# PCB_SATA_SFP.net
KiCad netlist of a schematic drawn in Altium Designer
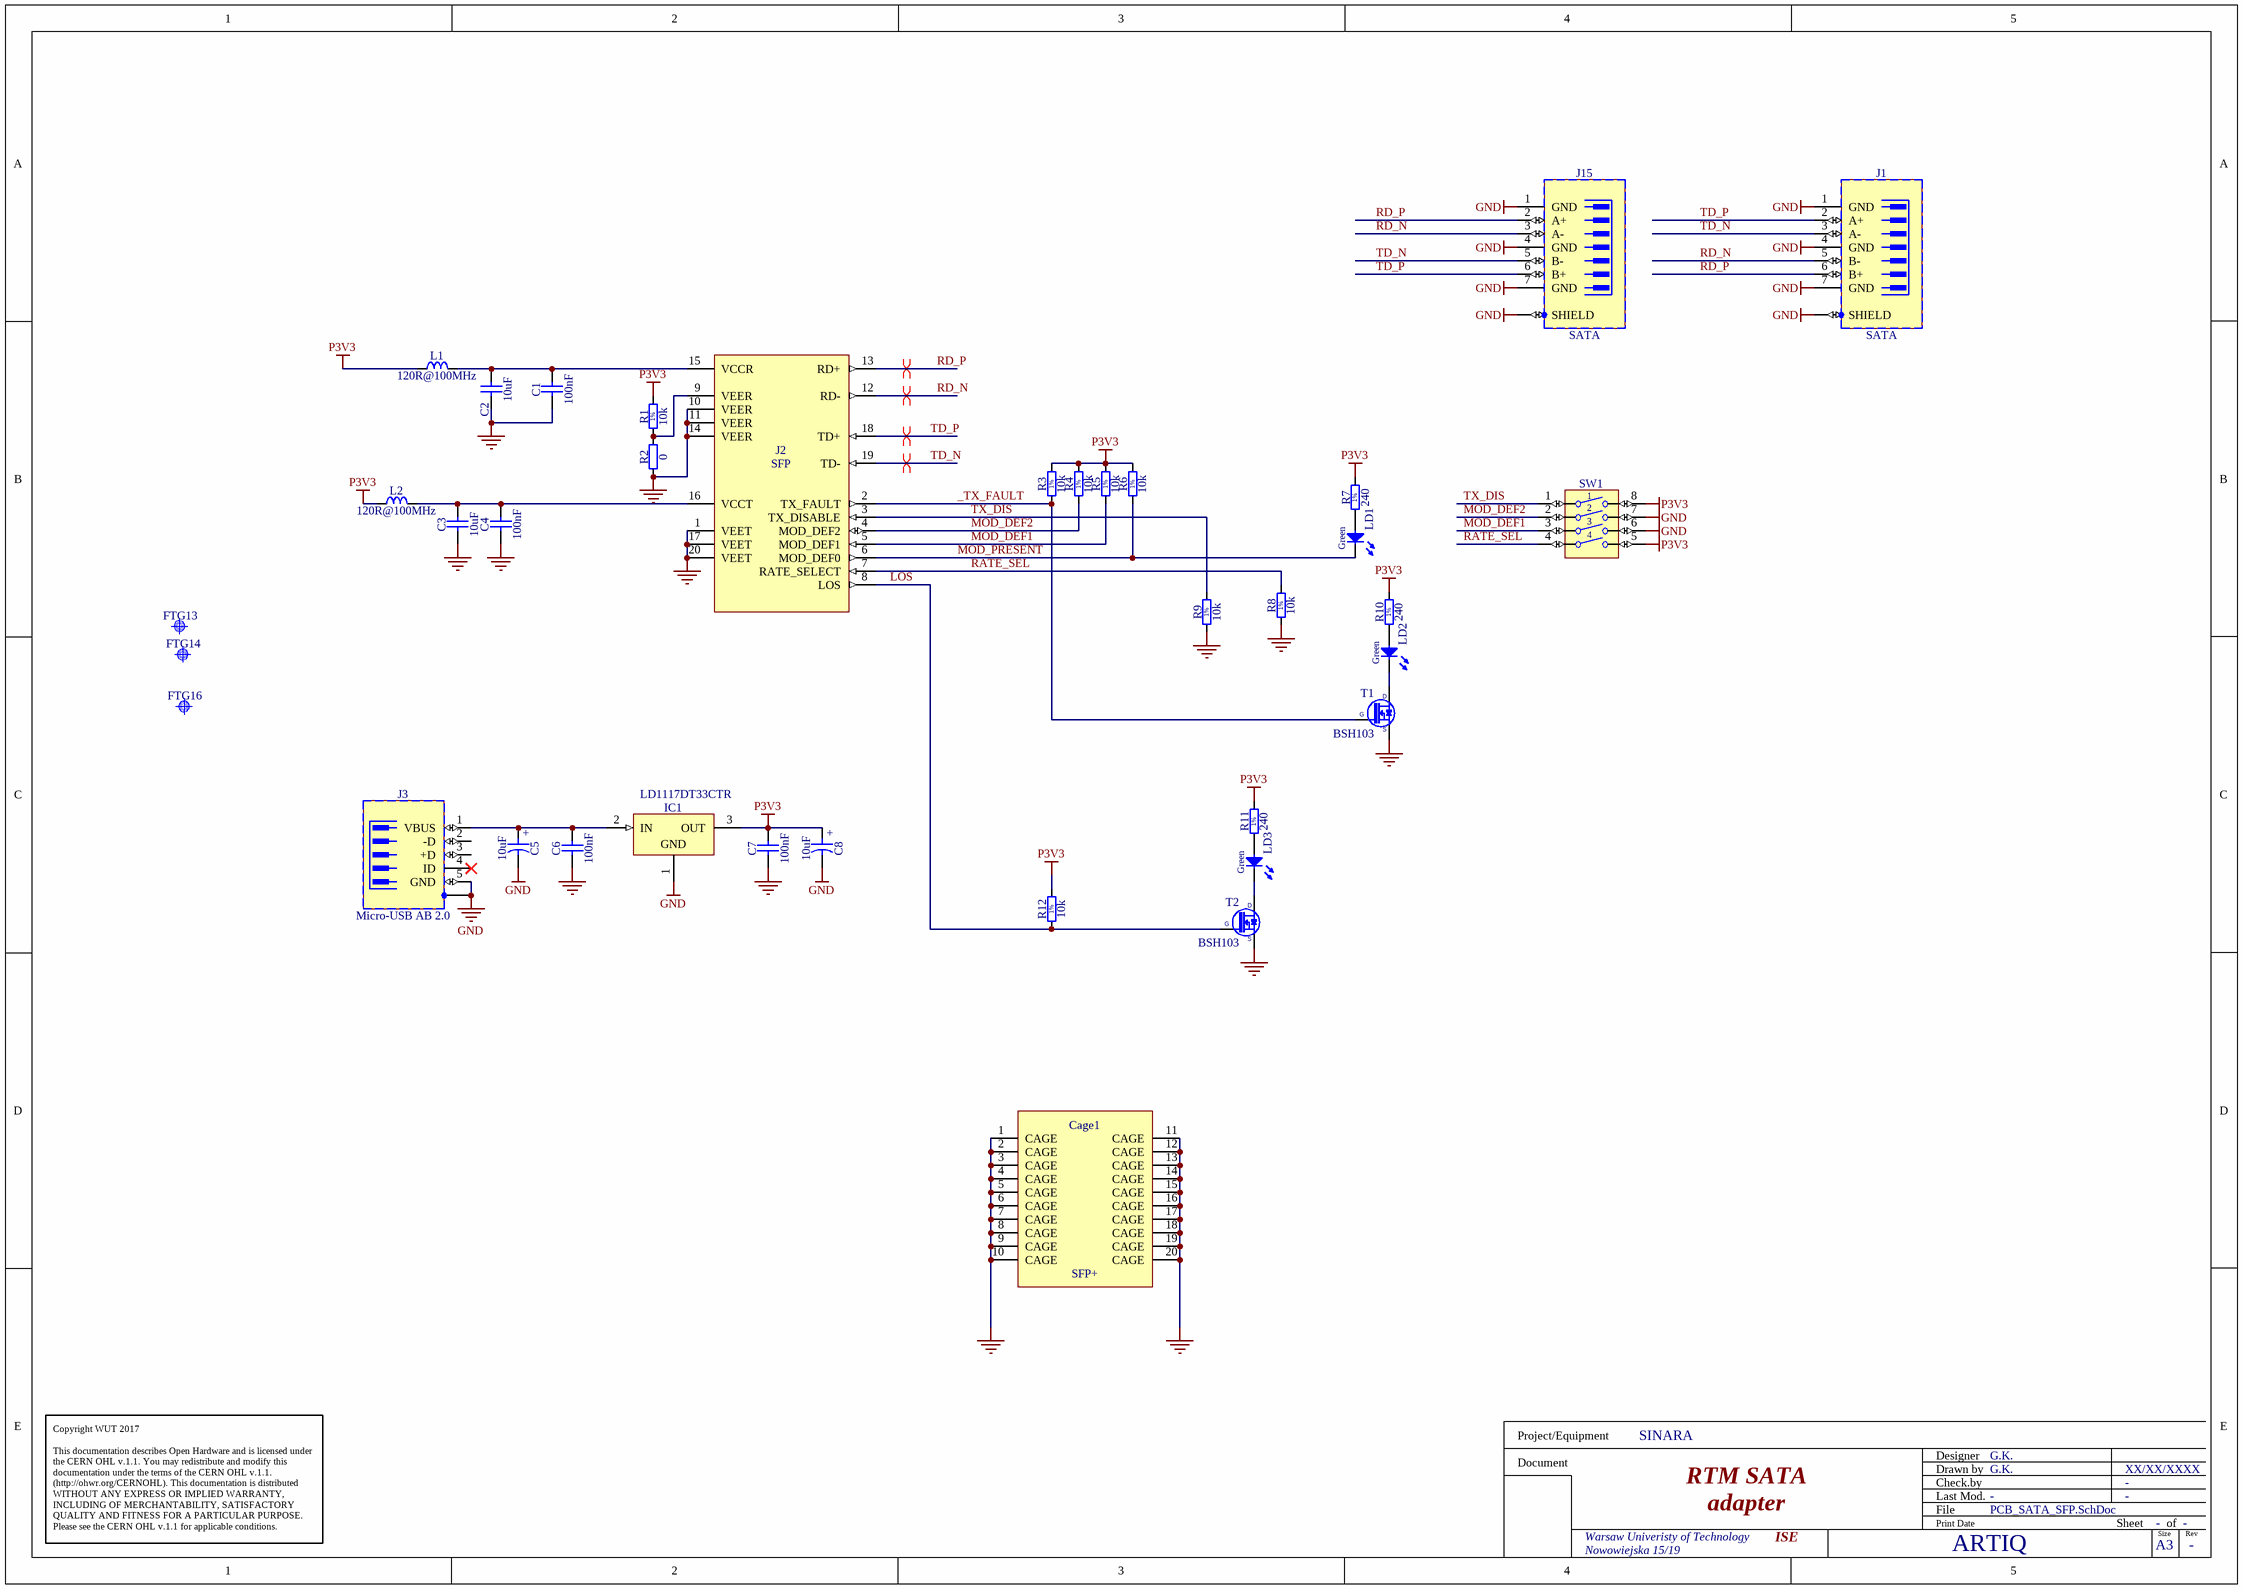
[diagram p0: PCB_SATA_SFP.SchDoc]

(export (version "E")
  (design (tool "Eeschema 10.0.6"))
  (components
    (comp (ref "C1")
      (value "100nF")
      (footprint "CAPC1608X87N")
      (description "Non-polarised capacitor")
      (fields
        (field (name "PART NUMBER") "CC0603_100NF_50V_10%_X5R")
        (field (name "VOLTAGE") "50V")
        (field (name "AUTHOR") "CERN DEM MR")
      )
      (libsource (lib "Capacitors") (part "Capacitor - non polarized"))
    )
    (comp (ref "C2")
      (value "10uF")
      (footprint "CAPC2012X95N")
      (description "Non-polarised capacitor")
      (fields
        (field (name "PART NUMBER") "CC0805_10UF_25V_10%_X5R")
        (field (name "VOLTAGE") "25V")
        (field (name "AUTHOR") "CERN DEM JLC")
      )
      (libsource (lib "Capacitors") (part "Capacitor - non polarized"))
    )
    (comp (ref "C3")
      (value "10uF")
      (footprint "CAPC2012X95N")
      (description "Non-polarised capacitor")
      (fields
        (field (name "PART NUMBER") "CC0805_10UF_25V_10%_X5R")
        (field (name "VOLTAGE") "25V")
        (field (name "AUTHOR") "CERN DEM JLC")
      )
      (libsource (lib "Capacitors") (part "Capacitor - non polarized"))
    )
    (comp (ref "C4")
      (value "100nF")
      (footprint "CAPC1608X87N")
      (description "Non-polarised capacitor")
      (fields
        (field (name "PART NUMBER") "CC0603_100NF_50V_10%_X5R")
        (field (name "VOLTAGE") "50V")
        (field (name "AUTHOR") "CERN DEM MR")
      )
      (libsource (lib "Capacitors") (part "Capacitor - non polarized"))
    )
    (comp (ref "C5")
      (value "10uF")
      (footprint "CAPMP6032X280N")
      (description "Polarised capacitor")
      (fields
        (field (name "PART NUMBER") "CTE6032-28_10UF_25V_10%_LESR0300")
        (field (name "VOLTAGE") "25V")
        (field (name "AUTHOR") "CERN DEM JLC")
      )
      (libsource (lib "Capacitors") (part "Capacitor - polarized"))
    )
    (comp (ref "C6")
      (value "100nF")
      (footprint "CAPC1608X87N")
      (description "Non-polarised capacitor")
      (fields
        (field (name "PART NUMBER") "CC0603_100NF_50V_10%_X5R")
        (field (name "VOLTAGE") "50V")
        (field (name "AUTHOR") "CERN DEM MR")
      )
      (libsource (lib "Capacitors") (part "Capacitor - non polarized"))
    )
    (comp (ref "C7")
      (value "100nF")
      (footprint "CAPC1608X87N")
      (description "Non-polarised capacitor")
      (fields
        (field (name "PART NUMBER") "CC0603_100NF_50V_10%_X5R")
        (field (name "VOLTAGE") "50V")
        (field (name "AUTHOR") "CERN DEM MR")
      )
      (libsource (lib "Capacitors") (part "Capacitor - non polarized"))
    )
    (comp (ref "C8")
      (value "10uF")
      (footprint "CAPMP6032X280N")
      (description "Polarised capacitor")
      (fields
        (field (name "PART NUMBER") "CTE6032-28_10UF_25V_10%_LESR0300")
        (field (name "VOLTAGE") "25V")
        (field (name "AUTHOR") "CERN DEM JLC")
      )
      (libsource (lib "Capacitors") (part "Capacitor - polarized"))
    )
    (comp (ref "Cage1")
      (value "SFP+")
      (footprint "TYCO_2007198-1")
      (description "SFP+ 1x1 Cage (20Pins)")
      (fields
        (field (name "PART NUMBER") "TYCO_2007198-1")
        (field (name "MANUFACTURER") "TYCO ELECTRONICS")
        (field (name "AUTHOR") "CERN DEM JLC")
      )
      (libsource (lib "Connectors") (part "SFP+ 1x1 Cage (20Pins)"))
    )
    (comp (ref "FTG13")
      (value "Use only in PCB")
      (footprint "FIDUCIAL_TOP_C100-200")
      (description "Fiducial Target")
      (fields (field (name "PART NUMBER") "FIDUCIAL_TARGET_C100-200") (field (name "AUTHOR") "CERN DEM JLC"))
      (libsource (lib "Eletro-mechanical") (part "Fiducial Target"))
    )
    (comp (ref "FTG14")
      (value "Use only in PCB")
      (footprint "FIDUCIAL_TOP_S100-200")
      (description "Fiducial Target")
      (fields (field (name "PART NUMBER") "FIDUCIAL_TARGET_S100-200") (field (name "AUTHOR") "CERN DEM JLC"))
      (libsource (lib "Eletro-mechanical") (part "Fiducial Target"))
    )
    (comp (ref "FTG16")
      (value "Use only in PCB")
      (footprint "FIDUCIAL_TOP_S100-200")
      (description "Fiducial Target")
      (fields (field (name "PART NUMBER") "FIDUCIAL_TARGET_S100-200") (field (name "AUTHOR") "CERN DEM JLC"))
      (libsource (lib "Eletro-mechanical") (part "Fiducial Target"))
    )
    (comp (ref "IC1")
      (value "LD1117DT33CTR")
      (footprint "TO228P972X240-3N-R540X510")
      (description "3-Terminal Regulator 1=GND 2=IN 3=OUT")
      (fields (field (name "MANUFACTURER") "ST MICROELECTRONICS") (field (name "AUTHOR") "CERN DEM JLC"))
      (libsource (lib "ICs And Semiconductors") (part "REG3 1GND-2IN-3OUT"))
    )
    (comp (ref "J1")
      (value "SATA")
      (footprint "3M_5607-4200-SH")
      (description "7 Pin + 1 Shield SATA Receptacle")
      (fields
        (field (name "PART NUMBER") "3M_5607-4200-SH")
        (field (name "MANUFACTURER") "3M")
        (field (name "AUTHOR") "CERN DEM JLC")
      )
      (libsource (lib "Connectors") (part "Connector SATA 7 Male + 1 Shield"))
    )
    (comp (ref "J2")
      (value "SFP")
      (footprint "TYCO_1367073-1")
      (description "20 Position SFP  Connector (Small Form-factor Pluggable)")
      (fields
        (field (name "PART NUMBER") "TYCO_1367073-1")
        (field (name "MANUFACTURER") "TYCO ELECTRONICS")
        (field (name "AUTHOR") "CERN DEM JLC")
      )
      (libsource (lib "Connectors") (part "SFPx1"))
    )
    (comp (ref "J3")
      (value "Micro-USB AB 2.0")
      (footprint "HIROSE_ZX62RD-AB-5P8")
      (description "5 Pin + 1 Shield USB Receptacle")
      (fields
        (field (name "PART NUMBER") "HIROSE_ZX62RD-AB-5P8")
        (field (name "MANUFACTURER") "HIROSE (HRS)")
        (field (name "AUTHOR") "CERN DEM JLC")
      )
      (libsource (lib "Connectors") (part "Connector USB 5 Pin + 1Shield"))
    )
    (comp (ref "J15")
      (value "SATA")
      (footprint "3M_5607-4200-SH")
      (description "7 Pin + 1 Shield SATA Receptacle")
      (fields
        (field (name "PART NUMBER") "3M_5607-4200-SH")
        (field (name "MANUFACTURER") "3M")
        (field (name "AUTHOR") "CERN DEM JLC")
      )
      (libsource (lib "Connectors") (part "Connector SATA 7 Male + 1 Shield"))
    )
    (comp (ref "L1")
      (value "120R@100MHz")
      (footprint "INDC1608X65N")
      (description "Inductor")
      (fields
        (field (name "PART NUMBER") "IND0603_MURATA_BLM18SG121TN1D")
        (field (name "POWER") "3A")
        (field (name "AUTHOR") "CERN DEM JLC")
      )
      (libsource (lib "Inductors & Transformers") (part "Inductor"))
    )
    (comp (ref "L2")
      (value "120R@100MHz")
      (footprint "INDC1608X65N")
      (description "Inductor")
      (fields
        (field (name "PART NUMBER") "IND0603_MURATA_BLM18SG121TN1D")
        (field (name "POWER") "3A")
        (field (name "AUTHOR") "CERN DEM JLC")
      )
      (libsource (lib "Inductors & Transformers") (part "Inductor"))
    )
    (comp (ref "LD1")
      (value "Green")
      (footprint "LED_KINGBRIGHT_KPH-1608CGCK")
      (description "LED Green 1C 2A")
      (fields
        (field (name "PART NUMBER") "LED_KINGBRIGHT_KPH-1608CGCK")
        (field (name "MANUFACTURER") "KINGBRIGHT")
        (field (name "AUTHOR") "CERN DEM JLC")
      )
      (libsource (lib "ICs And Semiconductors") (part "LED Green 1C 2A"))
    )
    (comp (ref "LD2")
      (value "Green")
      (footprint "LED_KINGBRIGHT_KPH-1608CGCK")
      (description "LED Green 1C 2A")
      (fields
        (field (name "PART NUMBER") "LED_KINGBRIGHT_KPH-1608CGCK")
        (field (name "MANUFACTURER") "KINGBRIGHT")
        (field (name "AUTHOR") "CERN DEM JLC")
      )
      (libsource (lib "ICs And Semiconductors") (part "LED Green 1C 2A"))
    )
    (comp (ref "LD3")
      (value "Green")
      (footprint "LED_KINGBRIGHT_KPH-1608CGCK")
      (description "LED Green 1C 2A")
      (fields
        (field (name "PART NUMBER") "LED_KINGBRIGHT_KPH-1608CGCK")
        (field (name "MANUFACTURER") "KINGBRIGHT")
        (field (name "AUTHOR") "CERN DEM JLC")
      )
      (libsource (lib "ICs And Semiconductors") (part "LED Green 1C 2A"))
    )
    (comp (ref "R1")
      (value "10k")
      (footprint "RESC1608X55N")
      (description "Resistor - 1%")
      (fields
        (field (name "PART NUMBER") "R0603_10K_1%_0.1W_100PPM")
        (field (name "POWER") "0.1W")
        (field (name "AUTHOR") "CERN DEM JLC")
      )
      (libsource (lib "Resistors") (part "Resistor - 1%"))
    )
    (comp (ref "R2")
      (value "0")
      (footprint "RESC1608X55N")
      (description "Resistor")
      (fields
        (field (name "PART NUMBER") "R0603_0R_JUMPER")
        (field (name "MANUFACTURER") "GENERIC")
        (field (name "AUTHOR") "CERN DEM JLC")
      )
      (libsource (lib "Resistors") (part "Resistor"))
    )
    (comp (ref "R3")
      (value "10k")
      (footprint "RESC1608X55N")
      (description "Resistor - 1%")
      (fields
        (field (name "PART NUMBER") "R0603_10K_1%_0.1W_100PPM")
        (field (name "POWER") "0.1W")
        (field (name "AUTHOR") "CERN DEM JLC")
      )
      (libsource (lib "Resistors") (part "Resistor - 1%"))
    )
    (comp (ref "R4")
      (value "10k")
      (footprint "RESC1608X55N")
      (description "Resistor - 1%")
      (fields
        (field (name "PART NUMBER") "R0603_10K_1%_0.1W_100PPM")
        (field (name "POWER") "0.1W")
        (field (name "AUTHOR") "CERN DEM JLC")
      )
      (libsource (lib "Resistors") (part "Resistor - 1%"))
    )
    (comp (ref "R5")
      (value "10k")
      (footprint "RESC1608X55N")
      (description "Resistor - 1%")
      (fields
        (field (name "PART NUMBER") "R0603_10K_1%_0.1W_100PPM")
        (field (name "POWER") "0.1W")
        (field (name "AUTHOR") "CERN DEM JLC")
      )
      (libsource (lib "Resistors") (part "Resistor - 1%"))
    )
    (comp (ref "R6")
      (value "10k")
      (footprint "RESC1608X55N")
      (description "Resistor - 1%")
      (fields
        (field (name "PART NUMBER") "R0603_10K_1%_0.1W_100PPM")
        (field (name "POWER") "0.1W")
        (field (name "AUTHOR") "CERN DEM JLC")
      )
      (libsource (lib "Resistors") (part "Resistor - 1%"))
    )
    (comp (ref "R7")
      (value "240")
      (footprint "RESC1608X55N")
      (description "Resistor - 1%")
      (fields
        (field (name "PART NUMBER") "R0603_240R_1%_0.1W_100PPM")
        (field (name "POWER") "0.1W")
        (field (name "AUTHOR") "CERN DEM JLC")
      )
      (libsource (lib "Resistors") (part "Resistor - 1%"))
    )
    (comp (ref "R8")
      (value "10k")
      (footprint "RESC1608X55N")
      (description "Resistor - 1%")
      (fields
        (field (name "PART NUMBER") "R0603_10K_1%_0.1W_100PPM")
        (field (name "POWER") "0.1W")
        (field (name "AUTHOR") "CERN DEM JLC")
      )
      (libsource (lib "Resistors") (part "Resistor - 1%"))
    )
    (comp (ref "R9")
      (value "10k")
      (footprint "RESC1608X55N")
      (description "Resistor - 1%")
      (fields
        (field (name "PART NUMBER") "R0603_10K_1%_0.1W_100PPM")
        (field (name "POWER") "0.1W")
        (field (name "AUTHOR") "CERN DEM JLC")
      )
      (libsource (lib "Resistors") (part "Resistor - 1%"))
    )
    (comp (ref "R10")
      (value "240")
      (footprint "RESC1608X55N")
      (description "Resistor - 1%")
      (fields
        (field (name "PART NUMBER") "R0603_240R_1%_0.1W_100PPM")
        (field (name "POWER") "0.1W")
        (field (name "AUTHOR") "CERN DEM JLC")
      )
      (libsource (lib "Resistors") (part "Resistor - 1%"))
    )
    (comp (ref "R11")
      (value "240")
      (footprint "RESC1608X55N")
      (description "Resistor - 1%")
      (fields
        (field (name "PART NUMBER") "R0603_240R_1%_0.1W_100PPM")
        (field (name "POWER") "0.1W")
        (field (name "AUTHOR") "CERN DEM JLC")
      )
      (libsource (lib "Resistors") (part "Resistor - 1%"))
    )
    (comp (ref "R12")
      (value "10k")
      (footprint "RESC1608X55N")
      (description "Resistor - 1%")
      (fields
        (field (name "PART NUMBER") "R0603_10K_1%_0.1W_100PPM")
        (field (name "POWER") "0.1W")
        (field (name "AUTHOR") "CERN DEM JLC")
      )
      (libsource (lib "Resistors") (part "Resistor - 1%"))
    )
    (comp (ref "SW1")
      (value "Switch")
      (footprint "SW_CTS_219-4MST")
      (description "4 Ways SPST DIP Switch")
      (fields
        (field (name "PART NUMBER") "SW_CTS_219-4MST")
        (field (name "MANUFACTURER") "CTS ELECTROCOMPONENTS")
        (field (name "AUTHOR") "CERN DEM JLC")
      )
      (libsource (lib "Eletro-mechanical") (part "SW 4x SPST DIP Switch"))
    )
    (comp (ref "T1")
      (value "BSH103")
      (footprint "SOT95P230X110-3N")
      (description "N-CHANNEL MOSFET WITH DIODE")
      (fields (field (name "MANUFACTURER") "NEXPERIA") (field (name "AUTHOR") "CERN DEM JLC"))
      (libsource (lib "ICs And Semiconductors") (part "N-MOSFET-D 1G 2S 3D"))
    )
    (comp (ref "T2")
      (value "BSH103")
      (footprint "SOT95P230X110-3N")
      (description "N-CHANNEL MOSFET WITH DIODE")
      (fields (field (name "MANUFACTURER") "NEXPERIA") (field (name "AUTHOR") "CERN DEM JLC"))
      (libsource (lib "ICs And Semiconductors") (part "N-MOSFET-D 1G 2S 3D"))
    )
  )
  (nets
    (net (code "1") (name "/LOS") (class "Default")
      (node (ref "J2") (pin "8") (pinfunction "LOS_8") (pintype "output"))
      (node (ref "R12") (pin "1") (pinfunction "1_1") (pintype "passive"))
      (node (ref "T2") (pin "1") (pinfunction "G_1") (pintype "passive"))
    )
    (net (code "2") (name "/MOD_DEF1") (class "Default")
      (node (ref "J2") (pin "5") (pinfunction "MOD_DEF1_5") (pintype "input"))
      (node (ref "R5") (pin "1") (pinfunction "1_1") (pintype "passive"))
      (node (ref "SW1") (pin "3") (pinfunction "3_3") (pintype "bidirectional"))
    )
    (net (code "3") (name "/MOD_DEF2") (class "Default")
      (node (ref "J2") (pin "4") (pinfunction "MOD_DEF2_4") (pintype "bidirectional"))
      (node (ref "R4") (pin "1") (pinfunction "1_1") (pintype "passive"))
      (node (ref "SW1") (pin "2") (pinfunction "2_2") (pintype "bidirectional"))
    )
    (net (code "4") (name "/MOD_PRESENT") (class "Default")
      (node (ref "J2") (pin "6") (pinfunction "MOD_DEF0_6") (pintype "output"))
      (node (ref "LD1") (pin "1") (pinfunction "C_1") (pintype "passive"))
      (node (ref "R6") (pin "1") (pinfunction "1_1") (pintype "passive"))
    )
    (net (code "5") (name "/RATE_SEL") (class "Default")
      (node (ref "J2") (pin "7") (pinfunction "RATE_SELECT_7") (pintype "input"))
      (node (ref "R8") (pin "2") (pinfunction "2_2") (pintype "passive"))
      (node (ref "SW1") (pin "4") (pinfunction "4_4") (pintype "bidirectional"))
    )
    (net (code "6") (name "/RD_N") (class "Default")
      (node (ref "J1") (pin "5") (pinfunction "B-_5") (pintype "bidirectional"))
      (node (ref "J15") (pin "3") (pinfunction "A-_3") (pintype "bidirectional"))
      (node (ref "J2") (pin "12") (pinfunction "RD-_12") (pintype "output"))
    )
    (net (code "7") (name "/RD_P") (class "Default")
      (node (ref "J1") (pin "6") (pinfunction "B+_6") (pintype "bidirectional"))
      (node (ref "J15") (pin "2") (pinfunction "A+_2") (pintype "bidirectional"))
      (node (ref "J2") (pin "13") (pinfunction "RD+_13") (pintype "output"))
    )
    (net (code "8") (name "/TD_N") (class "Default")
      (node (ref "J1") (pin "3") (pinfunction "A-_3") (pintype "bidirectional"))
      (node (ref "J15") (pin "5") (pinfunction "B-_5") (pintype "bidirectional"))
      (node (ref "J2") (pin "19") (pinfunction "TD-_19") (pintype "input"))
    )
    (net (code "9") (name "/TD_P") (class "Default")
      (node (ref "J1") (pin "2") (pinfunction "A+_2") (pintype "bidirectional"))
      (node (ref "J15") (pin "6") (pinfunction "B+_6") (pintype "bidirectional"))
      (node (ref "J2") (pin "18") (pinfunction "TD+_18") (pintype "input"))
    )
    (net (code "10") (name "/TX_DIS") (class "Default")
      (node (ref "J2") (pin "3") (pinfunction "TX_DISABLE_3") (pintype "input"))
      (node (ref "R9") (pin "2") (pinfunction "2_2") (pintype "passive"))
      (node (ref "SW1") (pin "1") (pinfunction "1_1") (pintype "bidirectional"))
    )
    (net (code "11") (name "/_TX_FAULT") (class "Default")
      (node (ref "J2") (pin "2") (pinfunction "TX_FAULT_2") (pintype "output"))
      (node (ref "R3") (pin "1") (pinfunction "1_1") (pintype "passive"))
      (node (ref "T1") (pin "1") (pinfunction "G_1") (pintype "passive"))
    )
    (net (code "12") (name "GND") (class "Default")
      (node (ref "C1") (pin "1") (pinfunction "1_1") (pintype "passive"))
      (node (ref "C2") (pin "1") (pinfunction "1_1") (pintype "passive"))
      (node (ref "C3") (pin "1") (pinfunction "1_1") (pintype "passive"))
      (node (ref "C4") (pin "1") (pinfunction "1_1") (pintype "passive"))
      (node (ref "C5") (pin "2") (pinfunction "2_2") (pintype "passive"))
      (node (ref "C6") (pin "1") (pinfunction "1_1") (pintype "passive"))
      (node (ref "C7") (pin "1") (pinfunction "1_1") (pintype "passive"))
      (node (ref "C8") (pin "2") (pinfunction "2_2") (pintype "passive"))
      (node (ref "Cage1") (pin "1") (pinfunction "CAGE_1") (pintype "power_in"))
      (node (ref "Cage1") (pin "10") (pinfunction "CAGE_10") (pintype "power_in"))
      (node (ref "Cage1") (pin "11") (pinfunction "CAGE_11") (pintype "power_in"))
      (node (ref "Cage1") (pin "12") (pinfunction "CAGE_12") (pintype "power_in"))
      (node (ref "Cage1") (pin "13") (pinfunction "CAGE_13") (pintype "power_in"))
      (node (ref "Cage1") (pin "14") (pinfunction "CAGE_14") (pintype "power_in"))
      (node (ref "Cage1") (pin "15") (pinfunction "CAGE_15") (pintype "power_in"))
      (node (ref "Cage1") (pin "16") (pinfunction "CAGE_16") (pintype "power_in"))
      (node (ref "Cage1") (pin "17") (pinfunction "CAGE_17") (pintype "power_in"))
      (node (ref "Cage1") (pin "18") (pinfunction "CAGE_18") (pintype "power_in"))
      (node (ref "Cage1") (pin "19") (pinfunction "CAGE_19") (pintype "power_in"))
      (node (ref "Cage1") (pin "2") (pinfunction "CAGE_2") (pintype "power_in"))
      (node (ref "Cage1") (pin "20") (pinfunction "CAGE_20") (pintype "power_in"))
      (node (ref "Cage1") (pin "3") (pinfunction "CAGE_3") (pintype "power_in"))
      (node (ref "Cage1") (pin "4") (pinfunction "CAGE_4") (pintype "power_in"))
      (node (ref "Cage1") (pin "5") (pinfunction "CAGE_5") (pintype "power_in"))
      (node (ref "Cage1") (pin "6") (pinfunction "CAGE_6") (pintype "power_in"))
      (node (ref "Cage1") (pin "7") (pinfunction "CAGE_7") (pintype "power_in"))
      (node (ref "Cage1") (pin "8") (pinfunction "CAGE_8") (pintype "power_in"))
      (node (ref "Cage1") (pin "9") (pinfunction "CAGE_9") (pintype "power_in"))
      (node (ref "IC1") (pin "1") (pinfunction "GND_1") (pintype "power_in"))
      (node (ref "J1") (pin "1") (pinfunction "GND_1") (pintype "power_in"))
      (node (ref "J1") (pin "4") (pinfunction "GND_4") (pintype "power_in"))
      (node (ref "J1") (pin "7") (pinfunction "GND_7") (pintype "power_in"))
      (node (ref "J1") (pin "8") (pinfunction "SHIELD_8") (pintype "bidirectional"))
      (node (ref "J15") (pin "1") (pinfunction "GND_1") (pintype "power_in"))
      (node (ref "J15") (pin "4") (pinfunction "GND_4") (pintype "power_in"))
      (node (ref "J15") (pin "7") (pinfunction "GND_7") (pintype "power_in"))
      (node (ref "J15") (pin "8") (pinfunction "SHIELD_8") (pintype "bidirectional"))
      (node (ref "J2") (pin "1") (pinfunction "VEET_1") (pintype "power_in"))
      (node (ref "J2") (pin "10") (pinfunction "VEER_10") (pintype "power_in"))
      (node (ref "J2") (pin "11") (pinfunction "VEER_11") (pintype "power_in"))
      (node (ref "J2") (pin "14") (pinfunction "VEER_14") (pintype "power_in"))
      (node (ref "J2") (pin "17") (pinfunction "VEET_17") (pintype "power_in"))
      (node (ref "J2") (pin "20") (pinfunction "VEET_20") (pintype "power_in"))
      (node (ref "J3") (pin "5") (pinfunction "GND_5") (pintype "bidirectional"))
      (node (ref "J3") (pin "6") (pinfunction "SH_6") (pintype "power_in"))
      (node (ref "R2") (pin "1") (pinfunction "1_1") (pintype "passive"))
      (node (ref "R8") (pin "1") (pinfunction "1_1") (pintype "passive"))
      (node (ref "R9") (pin "1") (pinfunction "1_1") (pintype "passive"))
      (node (ref "SW1") (pin "6") (pinfunction "6_6") (pintype "bidirectional"))
      (node (ref "SW1") (pin "7") (pinfunction "7_7") (pintype "bidirectional"))
      (node (ref "T1") (pin "2") (pinfunction "S_2") (pintype "passive"))
      (node (ref "T2") (pin "2") (pinfunction "S_2") (pintype "passive"))
    )
    (net (code "13") (name "Net-(IC1-IN)") (class "Default")
      (node (ref "C5") (pin "1") (pinfunction "1_1") (pintype "passive"))
      (node (ref "C6") (pin "2") (pinfunction "2_2") (pintype "passive"))
      (node (ref "IC1") (pin "2") (pinfunction "IN_2") (pintype "input"))
      (node (ref "J3") (pin "1") (pinfunction "VBUS_1") (pintype "bidirectional"))
    )
    (net (code "14") (name "Net-(J2-VCCR)") (class "Default")
      (node (ref "C1") (pin "2") (pinfunction "2_2") (pintype "passive"))
      (node (ref "C2") (pin "2") (pinfunction "2_2") (pintype "passive"))
      (node (ref "J2") (pin "15") (pinfunction "VCCR_15") (pintype "power_in"))
      (node (ref "L1") (pin "2") (pinfunction "2_2") (pintype "passive"))
    )
    (net (code "15") (name "Net-(J2-VCCT)") (class "Default")
      (node (ref "C3") (pin "2") (pinfunction "2_2") (pintype "passive"))
      (node (ref "C4") (pin "2") (pinfunction "2_2") (pintype "passive"))
      (node (ref "J2") (pin "16") (pinfunction "VCCT_16") (pintype "power_in"))
      (node (ref "L2") (pin "2") (pinfunction "2_2") (pintype "passive"))
    )
    (net (code "16") (name "Net-(J2-VEER-Pad9)") (class "Default")
      (node (ref "J2") (pin "9") (pinfunction "VEER_9") (pintype "power_in"))
      (node (ref "R1") (pin "1") (pinfunction "1_1") (pintype "passive"))
      (node (ref "R2") (pin "2") (pinfunction "2_2") (pintype "passive"))
    )
    (net (code "17") (name "Net-(LD1-A)") (class "Default")
      (node (ref "LD1") (pin "2") (pinfunction "A_2") (pintype "passive"))
      (node (ref "R7") (pin "1") (pinfunction "1_1") (pintype "passive"))
    )
    (net (code "18") (name "Net-(LD2-A)") (class "Default")
      (node (ref "LD2") (pin "2") (pinfunction "A_2") (pintype "passive"))
      (node (ref "R10") (pin "1") (pinfunction "1_1") (pintype "passive"))
    )
    (net (code "19") (name "Net-(LD2-C)") (class "Default")
      (node (ref "LD2") (pin "1") (pinfunction "C_1") (pintype "passive"))
      (node (ref "T1") (pin "3") (pinfunction "D_3") (pintype "passive"))
    )
    (net (code "20") (name "Net-(LD3-A)") (class "Default")
      (node (ref "LD3") (pin "2") (pinfunction "A_2") (pintype "passive"))
      (node (ref "R11") (pin "1") (pinfunction "1_1") (pintype "passive"))
    )
    (net (code "21") (name "Net-(LD3-C)") (class "Default")
      (node (ref "LD3") (pin "1") (pinfunction "C_1") (pintype "passive"))
      (node (ref "T2") (pin "3") (pinfunction "D_3") (pintype "passive"))
    )
    (net (code "22") (name "P3V3") (class "Default")
      (node (ref "C7") (pin "2") (pinfunction "2_2") (pintype "passive"))
      (node (ref "C8") (pin "1") (pinfunction "1_1") (pintype "passive"))
      (node (ref "IC1") (pin "3") (pinfunction "OUT_3") (pintype "power_in"))
      (node (ref "L1") (pin "1") (pinfunction "1_1") (pintype "passive"))
      (node (ref "L2") (pin "1") (pinfunction "1_1") (pintype "passive"))
      (node (ref "R1") (pin "2") (pinfunction "2_2") (pintype "passive"))
      (node (ref "R10") (pin "2") (pinfunction "2_2") (pintype "passive"))
      (node (ref "R11") (pin "2") (pinfunction "2_2") (pintype "passive"))
      (node (ref "R12") (pin "2") (pinfunction "2_2") (pintype "passive"))
      (node (ref "R3") (pin "2") (pinfunction "2_2") (pintype "passive"))
      (node (ref "R4") (pin "2") (pinfunction "2_2") (pintype "passive"))
      (node (ref "R5") (pin "2") (pinfunction "2_2") (pintype "passive"))
      (node (ref "R6") (pin "2") (pinfunction "2_2") (pintype "passive"))
      (node (ref "R7") (pin "2") (pinfunction "2_2") (pintype "passive"))
      (node (ref "SW1") (pin "5") (pinfunction "5_5") (pintype "bidirectional"))
      (node (ref "SW1") (pin "8") (pinfunction "8_8") (pintype "bidirectional"))
    )
    (net (code "23") (name "unconnected-(J3-+D-Pad3)") (class "Default")
      (node (ref "J3") (pin "3") (pinfunction "+D_3") (pintype "bidirectional"))
    )
    (net (code "24") (name "unconnected-(J3--D-Pad2)") (class "Default")
      (node (ref "J3") (pin "2") (pinfunction "-D_2") (pintype "bidirectional"))
    )
    (net (code "25") (name "unconnected-(J3-ID-Pad4)") (class "Default")
      (node (ref "J3") (pin "4") (pinfunction "ID_4") (pintype "passive+no_connect"))
    )
  )
)
